# IOP_1_0.net
KiCad netlist of a schematic drawn in EAGLE
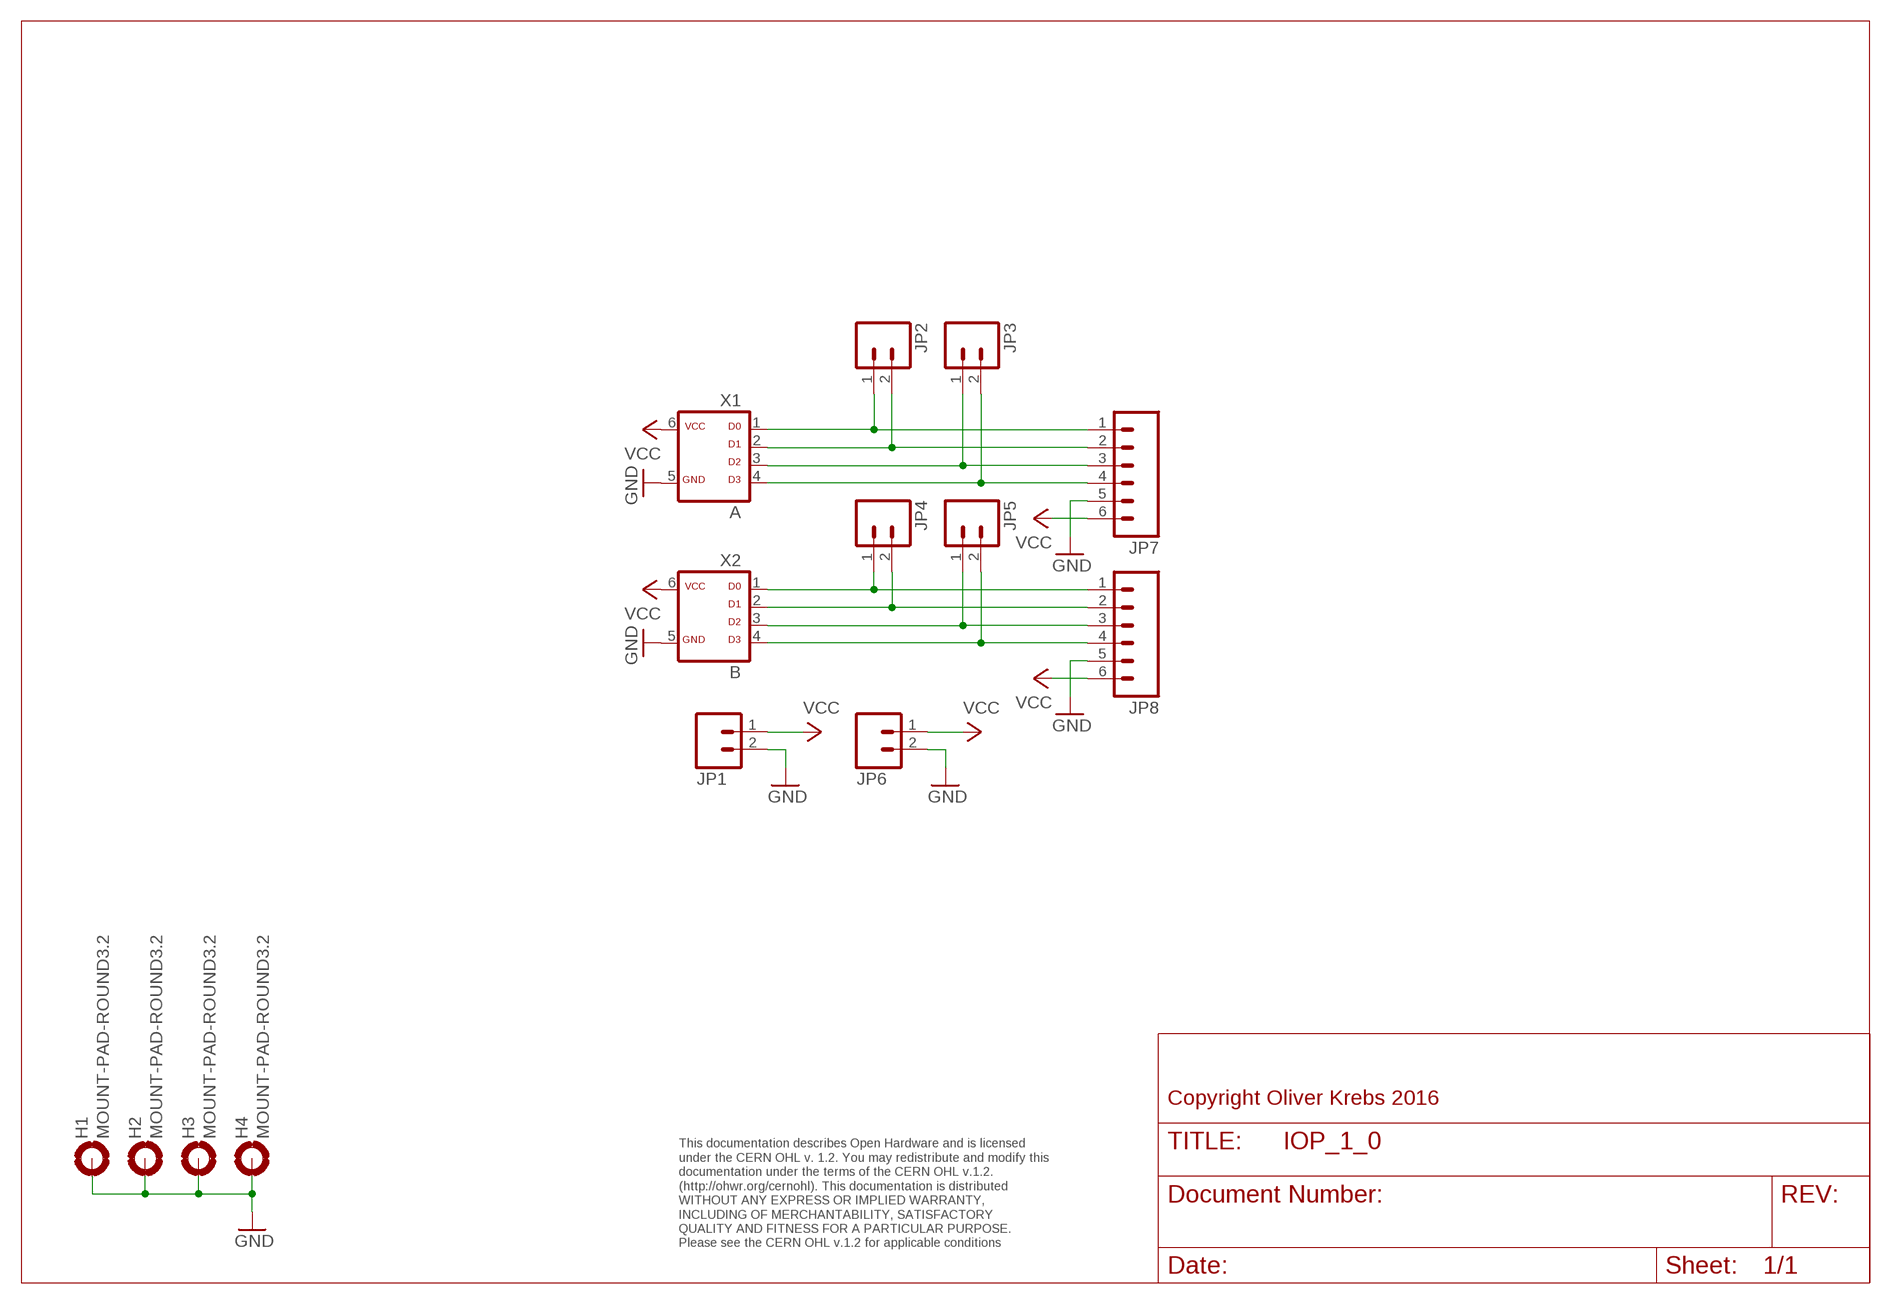
[diagram p0: schematic, sheet 1]

(export (version "E")
  (design (tool "Eeschema 10.0.6"))
  (components
    (comp (ref "H1")
      (value "MOUNT-PAD-ROUND3.2")
      (footprint "eagle-import:3,2-PAD")
      (libsource (lib "eagle-import") (part "MOUNT-PAD-ROUND3.2"))
    )
    (comp (ref "H2")
      (value "MOUNT-PAD-ROUND3.2")
      (footprint "eagle-import:3,2-PAD")
      (libsource (lib "eagle-import") (part "MOUNT-PAD-ROUND3.2"))
    )
    (comp (ref "H3")
      (value "MOUNT-PAD-ROUND3.2")
      (footprint "eagle-import:3,2-PAD")
      (libsource (lib "eagle-import") (part "MOUNT-PAD-ROUND3.2"))
    )
    (comp (ref "H4")
      (value "MOUNT-PAD-ROUND3.2")
      (footprint "eagle-import:3,2-PAD")
      (libsource (lib "eagle-import") (part "MOUNT-PAD-ROUND3.2"))
    )
    (comp (ref "JP1")
      (value "M021.3MM-5.08")
      (footprint "eagle-import:1X02_BIG_5.08")
      (libsource (lib "eagle-import") (part "M021.3MM-5.08"))
    )
    (comp (ref "JP2")
      (value "M021.3MM-5.08")
      (footprint "eagle-import:1X02_BIG_5.08")
      (libsource (lib "eagle-import") (part "M021.3MM-5.08"))
    )
    (comp (ref "JP3")
      (value "M021.3MM-5.08")
      (footprint "eagle-import:1X02_BIG_5.08")
      (libsource (lib "eagle-import") (part "M021.3MM-5.08"))
    )
    (comp (ref "JP4")
      (value "M021.3MM-5.08")
      (footprint "eagle-import:1X02_BIG_5.08")
      (libsource (lib "eagle-import") (part "M021.3MM-5.08"))
    )
    (comp (ref "JP5")
      (value "M021.3MM-5.08")
      (footprint "eagle-import:1X02_BIG_5.08")
      (libsource (lib "eagle-import") (part "M021.3MM-5.08"))
    )
    (comp (ref "JP6")
      (value "M021.3MM-5.08")
      (footprint "eagle-import:1X02_BIG_5.08")
      (libsource (lib "eagle-import") (part "M021.3MM-5.08"))
    )
    (comp (ref "JP7")
      (value "M06SILK_FEMALE_PTH")
      (footprint "eagle-import:1X06")
      (libsource (lib "eagle-import") (part "M06SILK_FEMALE_PTH"))
    )
    (comp (ref "JP8")
      (value "M06SILK_FEMALE_PTH")
      (footprint "eagle-import:1X06")
      (libsource (lib "eagle-import") (part "M06SILK_FEMALE_PTH"))
    )
    (comp (ref "X1")
      (value "A")
      (footprint "eagle-import:ML-6")
      (libsource (lib "eagle-import") (part "ML6D"))
    )
    (comp (ref "X2")
      (value "B")
      (footprint "eagle-import:ML-6")
      (libsource (lib "eagle-import") (part "ML6D"))
    )
  )
  (nets
    (net (code "1") (name "GND") (class "Default")
      (node (ref "H1") (pin "B3,2") (pinfunction "MOUNT_B3,2") (pintype "passive"))
      (node (ref "H2") (pin "B3,2") (pinfunction "MOUNT_B3,2") (pintype "passive"))
      (node (ref "H3") (pin "B3,2") (pinfunction "MOUNT_B3,2") (pintype "passive"))
      (node (ref "H4") (pin "B3,2") (pinfunction "MOUNT_B3,2") (pintype "passive"))
      (node (ref "JP1") (pin "2") (pinfunction "2_2") (pintype "passive"))
      (node (ref "JP6") (pin "2") (pinfunction "2_2") (pintype "passive"))
      (node (ref "JP7") (pin "5") (pinfunction "5_5") (pintype "passive"))
      (node (ref "JP8") (pin "5") (pinfunction "5_5") (pintype "passive"))
      (node (ref "X1") (pin "5") (pinfunction "5_5") (pintype "passive"))
      (node (ref "X2") (pin "5") (pinfunction "5_5") (pintype "passive"))
    )
    (net (code "2") (name "Net-(JP2-Pad1)") (class "Default")
      (node (ref "JP2") (pin "1") (pinfunction "1_1") (pintype "passive"))
      (node (ref "JP7") (pin "1") (pinfunction "1_1") (pintype "passive"))
      (node (ref "X1") (pin "1") (pinfunction "1_1") (pintype "passive"))
    )
    (net (code "3") (name "Net-(JP2-Pad2)") (class "Default")
      (node (ref "JP2") (pin "2") (pinfunction "2_2") (pintype "passive"))
      (node (ref "JP7") (pin "2") (pinfunction "2_2") (pintype "passive"))
      (node (ref "X1") (pin "2") (pinfunction "2_2") (pintype "passive"))
    )
    (net (code "4") (name "Net-(JP3-Pad1)") (class "Default")
      (node (ref "JP3") (pin "1") (pinfunction "1_1") (pintype "passive"))
      (node (ref "JP7") (pin "3") (pinfunction "3_3") (pintype "passive"))
      (node (ref "X1") (pin "3") (pinfunction "3_3") (pintype "passive"))
    )
    (net (code "5") (name "Net-(JP3-Pad2)") (class "Default")
      (node (ref "JP3") (pin "2") (pinfunction "2_2") (pintype "passive"))
      (node (ref "JP7") (pin "4") (pinfunction "4_4") (pintype "passive"))
      (node (ref "X1") (pin "4") (pinfunction "4_4") (pintype "passive"))
    )
    (net (code "6") (name "Net-(JP4-Pad1)") (class "Default")
      (node (ref "JP4") (pin "1") (pinfunction "1_1") (pintype "passive"))
      (node (ref "JP8") (pin "1") (pinfunction "1_1") (pintype "passive"))
      (node (ref "X2") (pin "1") (pinfunction "1_1") (pintype "passive"))
    )
    (net (code "7") (name "Net-(JP4-Pad2)") (class "Default")
      (node (ref "JP4") (pin "2") (pinfunction "2_2") (pintype "passive"))
      (node (ref "JP8") (pin "2") (pinfunction "2_2") (pintype "passive"))
      (node (ref "X2") (pin "2") (pinfunction "2_2") (pintype "passive"))
    )
    (net (code "8") (name "Net-(JP5-Pad1)") (class "Default")
      (node (ref "JP5") (pin "1") (pinfunction "1_1") (pintype "passive"))
      (node (ref "JP8") (pin "3") (pinfunction "3_3") (pintype "passive"))
      (node (ref "X2") (pin "3") (pinfunction "3_3") (pintype "passive"))
    )
    (net (code "9") (name "Net-(JP5-Pad2)") (class "Default")
      (node (ref "JP5") (pin "2") (pinfunction "2_2") (pintype "passive"))
      (node (ref "JP8") (pin "4") (pinfunction "4_4") (pintype "passive"))
      (node (ref "X2") (pin "4") (pinfunction "4_4") (pintype "passive"))
    )
    (net (code "10") (name "VCC") (class "Default")
      (node (ref "JP1") (pin "1") (pinfunction "1_1") (pintype "passive"))
      (node (ref "JP6") (pin "1") (pinfunction "1_1") (pintype "passive"))
      (node (ref "JP7") (pin "6") (pinfunction "6_6") (pintype "passive"))
      (node (ref "JP8") (pin "6") (pinfunction "6_6") (pintype "passive"))
      (node (ref "X1") (pin "6") (pinfunction "6_6") (pintype "passive"))
      (node (ref "X2") (pin "6") (pinfunction "6_6") (pintype "passive"))
    )
  )
)
